# Laser_Trip_Detector.net
KiCad netlist of a schematic drawn in EAGLE
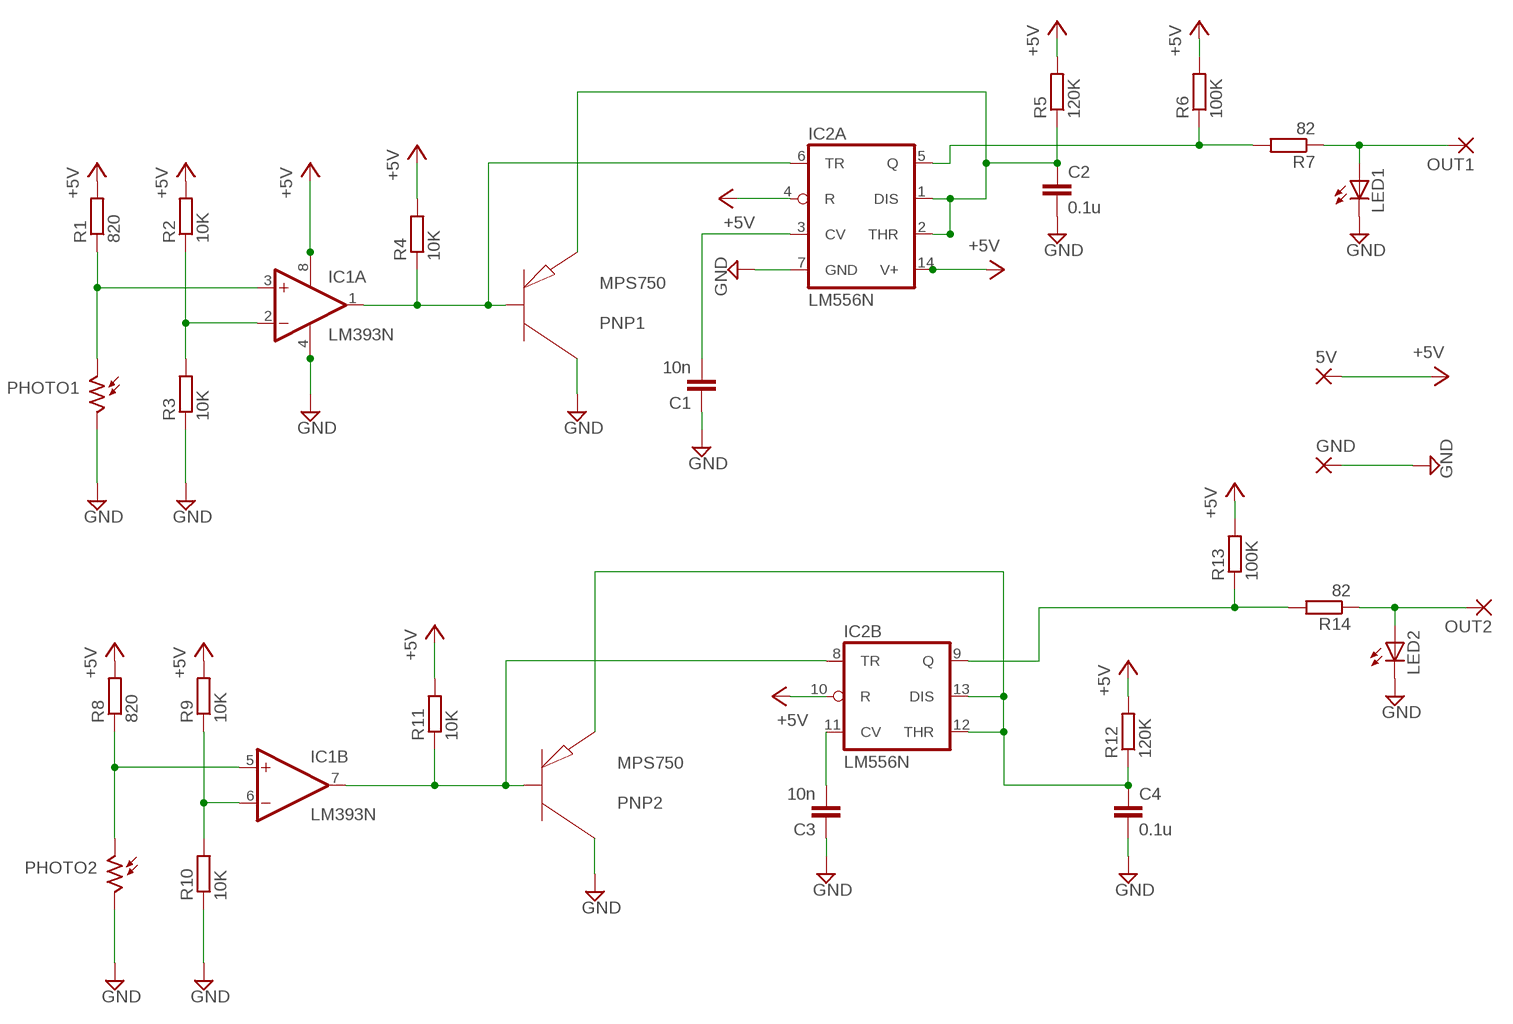
[diagram p0: schematic, sheet 1]

(export (version "E")
  (design (tool "Eeschema 10.0.6"))
  (components
    (comp (ref "5V")
      (value "3,17/1,3")
      (footprint "eagle-import:3,17_1,3")
      (libsource (lib "eagle-import") (part "3,17/1,3"))
    )
    (comp (ref "C1")
      (value "10n")
      (footprint "eagle-import:C5B3")
      (libsource (lib "eagle-import") (part "C5/3"))
    )
    (comp (ref "C2")
      (value "0.1u")
      (footprint "eagle-import:C5B3")
      (libsource (lib "eagle-import") (part "C5/3"))
    )
    (comp (ref "C3")
      (value "10n")
      (footprint "eagle-import:C5B3")
      (libsource (lib "eagle-import") (part "C5/3"))
    )
    (comp (ref "C4")
      (value "0.1u")
      (footprint "eagle-import:C5B3")
      (libsource (lib "eagle-import") (part "C5/3"))
    )
    (comp (ref "GND")
      (value "3,17/1,3")
      (footprint "eagle-import:3,17_1,3")
      (libsource (lib "eagle-import") (part "3,17/1,3"))
    )
    (comp (ref "IC1")
      (value "LM393N")
      (footprint "eagle-import:DIL08")
      (libsource (lib "eagle-import") (part "LM393N"))
    )
    (comp (ref "IC2")
      (value "LM556N")
      (footprint "eagle-import:DIL14")
      (libsource (lib "eagle-import") (part "556NLM"))
    )
    (comp (ref "LED1")
      (value "LED5MM")
      (footprint "eagle-import:LED5MM")
      (libsource (lib "eagle-import") (part "LED5MM"))
    )
    (comp (ref "LED2")
      (value "LED5MM")
      (footprint "eagle-import:LED5MM")
      (libsource (lib "eagle-import") (part "LED5MM"))
    )
    (comp (ref "OUT1")
      (value "3,17/1,3")
      (footprint "eagle-import:3,17_1,3")
      (libsource (lib "eagle-import") (part "3,17/1,3"))
    )
    (comp (ref "OUT2")
      (value "3,17/1,3")
      (footprint "eagle-import:3,17_1,3")
      (libsource (lib "eagle-import") (part "3,17/1,3"))
    )
    (comp (ref "PHOTO1")
      (value "M9960_11A")
      (footprint "eagle-import:M9960")
      (libsource (lib "eagle-import") (part "M9960_11A"))
    )
    (comp (ref "PHOTO2")
      (value "M9960_11A")
      (footprint "eagle-import:M9960")
      (libsource (lib "eagle-import") (part "M9960_11A"))
    )
    (comp (ref "PNP1")
      (value "MPS750")
      (footprint "eagle-import:TO92")
      (libsource (lib "eagle-import") (part "2N3906"))
    )
    (comp (ref "PNP2")
      (value "MPS750")
      (footprint "eagle-import:TO92")
      (libsource (lib "eagle-import") (part "2N3906"))
    )
    (comp (ref "R1")
      (value "820")
      (footprint "eagle-import:0207_10")
      (libsource (lib "eagle-import") (part "R0207/10"))
    )
    (comp (ref "R2")
      (value "10K")
      (footprint "eagle-import:0207_10")
      (libsource (lib "eagle-import") (part "R0207/10"))
    )
    (comp (ref "R3")
      (value "10K")
      (footprint "eagle-import:0207_10")
      (libsource (lib "eagle-import") (part "R0207/10"))
    )
    (comp (ref "R4")
      (value "10K")
      (footprint "eagle-import:0207_10")
      (libsource (lib "eagle-import") (part "R0207/10"))
    )
    (comp (ref "R5")
      (value "120K")
      (footprint "eagle-import:0207_10")
      (libsource (lib "eagle-import") (part "R0207/10"))
    )
    (comp (ref "R6")
      (value "100K")
      (footprint "eagle-import:0207_10")
      (libsource (lib "eagle-import") (part "R0207/10"))
    )
    (comp (ref "R7")
      (value "82")
      (footprint "eagle-import:0207_10")
      (libsource (lib "eagle-import") (part "R0207/10"))
    )
    (comp (ref "R8")
      (value "820")
      (footprint "eagle-import:0207_10")
      (libsource (lib "eagle-import") (part "R0207/10"))
    )
    (comp (ref "R9")
      (value "10K")
      (footprint "eagle-import:0207_10")
      (libsource (lib "eagle-import") (part "R0207/10"))
    )
    (comp (ref "R10")
      (value "10K")
      (footprint "eagle-import:0207_10")
      (libsource (lib "eagle-import") (part "R0207/10"))
    )
    (comp (ref "R11")
      (value "10K")
      (footprint "eagle-import:0207_10")
      (libsource (lib "eagle-import") (part "R0207/10"))
    )
    (comp (ref "R12")
      (value "120K")
      (footprint "eagle-import:0207_10")
      (libsource (lib "eagle-import") (part "R0207/10"))
    )
    (comp (ref "R13")
      (value "100K")
      (footprint "eagle-import:0207_10")
      (libsource (lib "eagle-import") (part "R0207/10"))
    )
    (comp (ref "R14")
      (value "82")
      (footprint "eagle-import:0207_10")
      (libsource (lib "eagle-import") (part "R0207/10"))
    )
  )
  (nets
    (net (code "1") (name "+5V") (class "Default")
      (node (ref "5V") (pin "1") (pinfunction "P_1") (pintype "passive"))
      (node (ref "IC1") (pin "8") (pinfunction "V+_8") (pintype "power_in"))
      (node (ref "IC2") (pin "10") (pinfunction "R_10") (pintype "input"))
      (node (ref "IC2") (pin "14") (pinfunction "V+_14") (pintype "power_in"))
      (node (ref "IC2") (pin "4") (pinfunction "R_4") (pintype "input"))
      (node (ref "R1") (pin "2") (pinfunction "2_2") (pintype "passive"))
      (node (ref "R11") (pin "2") (pinfunction "2_2") (pintype "passive"))
      (node (ref "R12") (pin "2") (pinfunction "2_2") (pintype "passive"))
      (node (ref "R13") (pin "2") (pinfunction "2_2") (pintype "passive"))
      (node (ref "R2") (pin "2") (pinfunction "2_2") (pintype "passive"))
      (node (ref "R4") (pin "2") (pinfunction "2_2") (pintype "passive"))
      (node (ref "R5") (pin "2") (pinfunction "2_2") (pintype "passive"))
      (node (ref "R6") (pin "2") (pinfunction "2_2") (pintype "passive"))
      (node (ref "R8") (pin "2") (pinfunction "2_2") (pintype "passive"))
      (node (ref "R9") (pin "2") (pinfunction "2_2") (pintype "passive"))
    )
    (net (code "2") (name "GND") (class "Default")
      (node (ref "C1") (pin "1") (pinfunction "1_1") (pintype "passive"))
      (node (ref "C2") (pin "2") (pinfunction "2_2") (pintype "passive"))
      (node (ref "C3") (pin "1") (pinfunction "1_1") (pintype "passive"))
      (node (ref "C4") (pin "2") (pinfunction "2_2") (pintype "passive"))
      (node (ref "GND") (pin "1") (pinfunction "P_1") (pintype "passive"))
      (node (ref "IC1") (pin "4") (pinfunction "V-_4") (pintype "power_in"))
      (node (ref "IC2") (pin "7") (pinfunction "GND_7") (pintype "power_in"))
      (node (ref "LED1") (pin "K") (pinfunction "C_K") (pintype "passive"))
      (node (ref "LED2") (pin "K") (pinfunction "C_K") (pintype "passive"))
      (node (ref "PHOTO1") (pin "2") (pinfunction "2_2") (pintype "passive"))
      (node (ref "PHOTO2") (pin "2") (pinfunction "2_2") (pintype "passive"))
      (node (ref "PNP1") (pin "1") (pinfunction "C_1") (pintype "passive"))
      (node (ref "PNP2") (pin "1") (pinfunction "C_1") (pintype "passive"))
      (node (ref "R10") (pin "1") (pinfunction "1_1") (pintype "passive"))
      (node (ref "R3") (pin "1") (pinfunction "1_1") (pintype "passive"))
    )
    (net (code "3") (name "Net-(IC1A-+IN)") (class "Default")
      (node (ref "IC1") (pin "3") (pinfunction "+IN_3") (pintype "input"))
      (node (ref "PHOTO1") (pin "1") (pinfunction "1_1") (pintype "passive"))
      (node (ref "R1") (pin "1") (pinfunction "1_1") (pintype "passive"))
    )
    (net (code "4") (name "Net-(IC1A--IN)") (class "Default")
      (node (ref "IC1") (pin "2") (pinfunction "-IN_2") (pintype "input"))
      (node (ref "R2") (pin "1") (pinfunction "1_1") (pintype "passive"))
      (node (ref "R3") (pin "2") (pinfunction "2_2") (pintype "passive"))
    )
    (net (code "5") (name "Net-(IC1A-OUT)") (class "Default")
      (node (ref "IC1") (pin "1") (pinfunction "OUT_1") (pintype "output"))
      (node (ref "IC2") (pin "6") (pinfunction "TR_6") (pintype "input"))
      (node (ref "PNP1") (pin "2") (pinfunction "B_2") (pintype "passive"))
      (node (ref "R4") (pin "1") (pinfunction "1_1") (pintype "passive"))
    )
    (net (code "6") (name "Net-(IC1B-+IN)") (class "Default")
      (node (ref "IC1") (pin "5") (pinfunction "+IN_5") (pintype "input"))
      (node (ref "PHOTO2") (pin "1") (pinfunction "1_1") (pintype "passive"))
      (node (ref "R8") (pin "1") (pinfunction "1_1") (pintype "passive"))
    )
    (net (code "7") (name "Net-(IC1B--IN)") (class "Default")
      (node (ref "IC1") (pin "6") (pinfunction "-IN_6") (pintype "input"))
      (node (ref "R10") (pin "2") (pinfunction "2_2") (pintype "passive"))
      (node (ref "R9") (pin "1") (pinfunction "1_1") (pintype "passive"))
    )
    (net (code "8") (name "Net-(IC1B-OUT)") (class "Default")
      (node (ref "IC1") (pin "7") (pinfunction "OUT_7") (pintype "output"))
      (node (ref "IC2") (pin "8") (pinfunction "TR_8") (pintype "input"))
      (node (ref "PNP2") (pin "2") (pinfunction "B_2") (pintype "passive"))
      (node (ref "R11") (pin "1") (pinfunction "1_1") (pintype "passive"))
    )
    (net (code "9") (name "Net-(IC2A-CV)") (class "Default")
      (node (ref "C1") (pin "2") (pinfunction "2_2") (pintype "passive"))
      (node (ref "IC2") (pin "3") (pinfunction "CV_3") (pintype "input"))
    )
    (net (code "10") (name "Net-(IC2A-DIS)") (class "Default")
      (node (ref "C2") (pin "1") (pinfunction "1_1") (pintype "passive"))
      (node (ref "IC2") (pin "1") (pinfunction "DIS_1") (pintype "input"))
      (node (ref "IC2") (pin "2") (pinfunction "THR_2") (pintype "input"))
      (node (ref "PNP1") (pin "3") (pinfunction "E_3") (pintype "passive"))
      (node (ref "R5") (pin "1") (pinfunction "1_1") (pintype "passive"))
    )
    (net (code "11") (name "Net-(IC2A-Q)") (class "Default")
      (node (ref "IC2") (pin "5") (pinfunction "Q_5") (pintype "output"))
      (node (ref "R6") (pin "1") (pinfunction "1_1") (pintype "passive"))
      (node (ref "R7") (pin "2") (pinfunction "2_2") (pintype "passive"))
    )
    (net (code "12") (name "Net-(IC2B-CV)") (class "Default")
      (node (ref "C3") (pin "2") (pinfunction "2_2") (pintype "passive"))
      (node (ref "IC2") (pin "11") (pinfunction "CV_11") (pintype "input"))
    )
    (net (code "13") (name "Net-(IC2B-DIS)") (class "Default")
      (node (ref "C4") (pin "1") (pinfunction "1_1") (pintype "passive"))
      (node (ref "IC2") (pin "12") (pinfunction "THR_12") (pintype "input"))
      (node (ref "IC2") (pin "13") (pinfunction "DIS_13") (pintype "input"))
      (node (ref "PNP2") (pin "3") (pinfunction "E_3") (pintype "passive"))
      (node (ref "R12") (pin "1") (pinfunction "1_1") (pintype "passive"))
    )
    (net (code "14") (name "Net-(IC2B-Q)") (class "Default")
      (node (ref "IC2") (pin "9") (pinfunction "Q_9") (pintype "output"))
      (node (ref "R13") (pin "1") (pinfunction "1_1") (pintype "passive"))
      (node (ref "R14") (pin "2") (pinfunction "2_2") (pintype "passive"))
    )
    (net (code "15") (name "Net-(OUT1-P)") (class "Default")
      (node (ref "LED1") (pin "A") (pinfunction "A_A") (pintype "passive"))
      (node (ref "OUT1") (pin "1") (pinfunction "P_1") (pintype "passive"))
      (node (ref "R7") (pin "1") (pinfunction "1_1") (pintype "passive"))
    )
    (net (code "16") (name "Net-(OUT2-P)") (class "Default")
      (node (ref "LED2") (pin "A") (pinfunction "A_A") (pintype "passive"))
      (node (ref "OUT2") (pin "1") (pinfunction "P_1") (pintype "passive"))
      (node (ref "R14") (pin "1") (pinfunction "1_1") (pintype "passive"))
    )
  )
)
